# 8ChanDirTranslation.net
KiCad netlist of a schematic drawn in Altium Designer
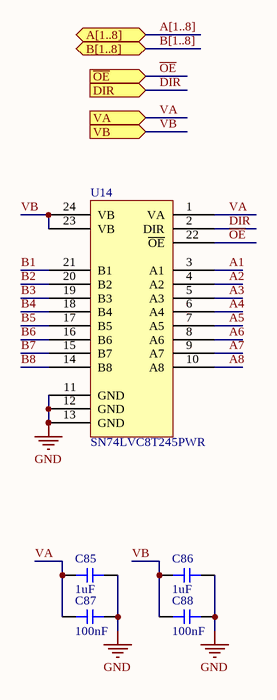
[diagram p0: 8ChanDirTranslation.SchDoc]

(export (version "E")
  (design (tool "Eeschema 10.0.6"))
  (components
    (comp (ref "C85")
      (value "1uF")
      (footprint "0603-CAP")
      (description "Capacitor")
      (libsource (lib "AMDC") (part "Capacitor"))
    )
    (comp (ref "C86")
      (value "1uF")
      (footprint "0603-CAP")
      (description "Capacitor")
      (libsource (lib "AMDC") (part "Capacitor"))
    )
    (comp (ref "C87")
      (value "100nF")
      (footprint "0603-CAP")
      (description "Capacitor")
      (libsource (lib "AMDC") (part "Capacitor"))
    )
    (comp (ref "C88")
      (value "100nF")
      (footprint "0603-CAP")
      (description "Capacitor")
      (libsource (lib "AMDC") (part "Capacitor"))
    )
    (comp (ref "U14")
      (value "SN74LVC8T245PWR")
      (footprint "TSSOP24")
      (description "IC BUS TRANSCVR 8BIT 24TSSOP")
      (libsource (lib "AMDC") (part "SN74LVC8T245PWR"))
    )
  )
  (nets
    (net (code "1") (name "/A1") (class "Default")
      (node (ref "U14") (pin "3") (pinfunction "A1_3") (pintype "passive"))
    )
    (net (code "2") (name "/A2") (class "Default")
      (node (ref "U14") (pin "4") (pinfunction "A2_4") (pintype "passive"))
    )
    (net (code "3") (name "/A3") (class "Default")
      (node (ref "U14") (pin "5") (pinfunction "A3_5") (pintype "passive"))
    )
    (net (code "4") (name "/A4") (class "Default")
      (node (ref "U14") (pin "6") (pinfunction "A4_6") (pintype "passive"))
    )
    (net (code "5") (name "/A5") (class "Default")
      (node (ref "U14") (pin "7") (pinfunction "A5_7") (pintype "passive"))
    )
    (net (code "6") (name "/A6") (class "Default")
      (node (ref "U14") (pin "8") (pinfunction "A6_8") (pintype "passive"))
    )
    (net (code "7") (name "/A7") (class "Default")
      (node (ref "U14") (pin "9") (pinfunction "A7_9") (pintype "passive"))
    )
    (net (code "8") (name "/A8") (class "Default")
      (node (ref "U14") (pin "10") (pinfunction "A8_10") (pintype "passive"))
    )
    (net (code "10") (name "/B1") (class "Default")
      (node (ref "U14") (pin "21") (pinfunction "B1_21") (pintype "passive"))
    )
    (net (code "11") (name "/B2") (class "Default")
      (node (ref "U14") (pin "20") (pinfunction "B2_20") (pintype "passive"))
    )
    (net (code "12") (name "/B3") (class "Default")
      (node (ref "U14") (pin "19") (pinfunction "B3_19") (pintype "passive"))
    )
    (net (code "13") (name "/B4") (class "Default")
      (node (ref "U14") (pin "18") (pinfunction "B4_18") (pintype "passive"))
    )
    (net (code "14") (name "/B5") (class "Default")
      (node (ref "U14") (pin "17") (pinfunction "B5_17") (pintype "passive"))
    )
    (net (code "15") (name "/B6") (class "Default")
      (node (ref "U14") (pin "16") (pinfunction "B6_16") (pintype "passive"))
    )
    (net (code "16") (name "/B7") (class "Default")
      (node (ref "U14") (pin "15") (pinfunction "B7_15") (pintype "passive"))
    )
    (net (code "17") (name "/B8") (class "Default")
      (node (ref "U14") (pin "14") (pinfunction "B8_14") (pintype "passive"))
    )
    (net (code "19") (name "/DIR") (class "Default")
      (node (ref "U14") (pin "2") (pinfunction "DIR_2") (pintype "passive"))
    )
    (net (code "20") (name "/VA") (class "Default")
      (node (ref "C85") (pin "1") (pinfunction "1_1") (pintype "passive"))
      (node (ref "C87") (pin "1") (pinfunction "1_1") (pintype "passive"))
      (node (ref "U14") (pin "1") (pinfunction "VA_1") (pintype "passive"))
    )
    (net (code "21") (name "/VB") (class "Default")
      (node (ref "C86") (pin "1") (pinfunction "1_1") (pintype "passive"))
      (node (ref "C88") (pin "1") (pinfunction "1_1") (pintype "passive"))
      (node (ref "U14") (pin "23") (pinfunction "VB_23") (pintype "passive"))
      (node (ref "U14") (pin "24") (pinfunction "VB_24") (pintype "passive"))
    )
    (net (code "22") (name "/~{OE}") (class "Default")
      (node (ref "U14") (pin "22") (pinfunction "~{OE}_22") (pintype "passive"))
    )
    (net (code "23") (name "GND") (class "Default")
      (node (ref "C85") (pin "2") (pinfunction "2_2") (pintype "passive"))
      (node (ref "C86") (pin "2") (pinfunction "2_2") (pintype "passive"))
      (node (ref "C87") (pin "2") (pinfunction "2_2") (pintype "passive"))
      (node (ref "C88") (pin "2") (pinfunction "2_2") (pintype "passive"))
      (node (ref "U14") (pin "11") (pinfunction "GND_11") (pintype "passive"))
      (node (ref "U14") (pin "12") (pinfunction "GND_12") (pintype "passive"))
      (node (ref "U14") (pin "13") (pinfunction "GND_13") (pintype "passive"))
    )
  )
)
